# servusb.net
KiCad netlist of a schematic drawn in EAGLE
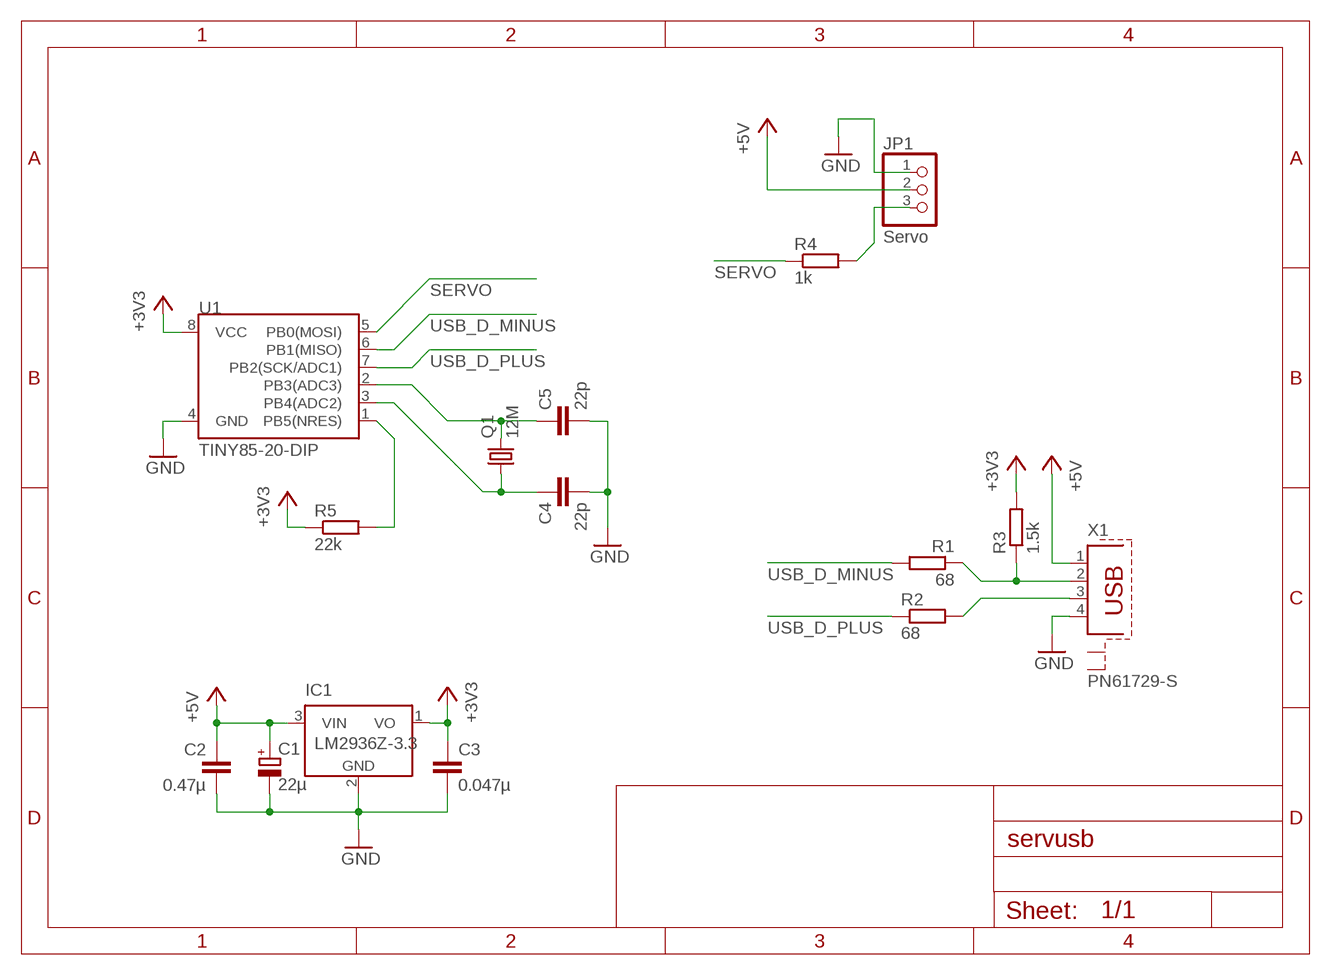
[diagram p0: schematic, sheet 1]

(export (version "E")
  (design (tool "Eeschema 10.0.6"))
  (components
    (comp (ref "C1")
      (value "22µ")
      (footprint "eagle-import:E2,5-6")
      (libsource (lib "eagle-import") (part "CPOL-EUE2.5-6"))
    )
    (comp (ref "C2")
      (value "0.47µ")
      (footprint "eagle-import:C075-042X103")
      (libsource (lib "eagle-import") (part "C-EU075-042X103"))
    )
    (comp (ref "C3")
      (value "0.047µ")
      (footprint "eagle-import:C050-025X075")
      (libsource (lib "eagle-import") (part "C-EU050-025X075"))
    )
    (comp (ref "C4")
      (value "22p")
      (footprint "eagle-import:C025-024X044")
      (libsource (lib "eagle-import") (part "C-EU025-024X044"))
    )
    (comp (ref "C5")
      (value "22p")
      (footprint "eagle-import:C025-024X044")
      (libsource (lib "eagle-import") (part "C-EU025-024X044"))
    )
    (comp (ref "IC1")
      (value "LM2936Z-3.3")
      (footprint "eagle-import:TO92")
      (fields (field (name "MF") "NATIONAL SEMICONDUCTOR") (field (name "MPN") "LM2936Z-3.3/NOPB"))
      (libsource (lib "eagle-import") (part "LM2936?Z-3.3"))
    )
    (comp (ref "JP1")
      (value "Servo")
      (footprint "eagle-import:1X03")
      (libsource (lib "eagle-import") (part "PINHD-1X3"))
    )
    (comp (ref "Q1")
      (value "12M")
      (footprint "eagle-import:HC49_S")
      (libsource (lib "eagle-import") (part "CRYSTALHC49S"))
    )
    (comp (ref "R1")
      (value "68")
      (footprint "eagle-import:0204_7")
      (libsource (lib "eagle-import") (part "R-EU_0204/7"))
    )
    (comp (ref "R2")
      (value "68")
      (footprint "eagle-import:0204_7")
      (libsource (lib "eagle-import") (part "R-EU_0204/7"))
    )
    (comp (ref "R3")
      (value "1.5k")
      (footprint "eagle-import:0204_7")
      (libsource (lib "eagle-import") (part "R-EU_0204/7"))
    )
    (comp (ref "R4")
      (value "1k")
      (footprint "eagle-import:0204_7")
      (libsource (lib "eagle-import") (part "R-EU_0204/7"))
    )
    (comp (ref "R5")
      (value "22k")
      (footprint "eagle-import:0204_7")
      (libsource (lib "eagle-import") (part "R-EU_0204/7"))
    )
    (comp (ref "U1")
      (value "TINY85-20-DIP")
      (footprint "eagle-import:DIP08")
      (libsource (lib "eagle-import") (part "ATTINY45TINY85-20-DIP"))
    )
    (comp (ref "X1")
      (value "PN61729-S")
      (footprint "eagle-import:PN61729-S")
      (libsource (lib "eagle-import") (part "PN61729-S"))
    )
  )
  (nets
    (net (code "1") (name "+3V3") (class "Default")
      (node (ref "C3") (pin "1") (pinfunction "1_1") (pintype "passive"))
      (node (ref "IC1") (pin "1") (pinfunction "VO_1") (pintype "passive"))
      (node (ref "R3") (pin "2") (pinfunction "2_2") (pintype "passive"))
      (node (ref "R5") (pin "1") (pinfunction "1_1") (pintype "passive"))
      (node (ref "U1") (pin "8") (pinfunction "VCC_8") (pintype "bidirectional"))
    )
    (net (code "2") (name "+5V") (class "Default")
      (node (ref "C1") (pin "+") (pinfunction "+_+") (pintype "passive"))
      (node (ref "C2") (pin "1") (pinfunction "1_1") (pintype "passive"))
      (node (ref "IC1") (pin "3") (pinfunction "VIN_3") (pintype "input"))
      (node (ref "JP1") (pin "2") (pinfunction "2_2") (pintype "passive"))
      (node (ref "X1") (pin "1") (pinfunction "1_1") (pintype "passive"))
    )
    (net (code "3") (name "/SERVO") (class "Default")
      (node (ref "R4") (pin "1") (pinfunction "1_1") (pintype "passive"))
      (node (ref "U1") (pin "5") (pinfunction "PB0(MOSI)_5") (pintype "bidirectional"))
    )
    (net (code "4") (name "/USB_D_MINUS") (class "Default")
      (node (ref "R1") (pin "2") (pinfunction "2_2") (pintype "passive"))
      (node (ref "U1") (pin "6") (pinfunction "PB1(MISO)_6") (pintype "bidirectional"))
    )
    (net (code "5") (name "/USB_D_PLUS") (class "Default")
      (node (ref "R2") (pin "1") (pinfunction "1_1") (pintype "passive"))
      (node (ref "U1") (pin "7") (pinfunction "PB2(SCK/ADC1)_7") (pintype "bidirectional"))
    )
    (net (code "6") (name "GND") (class "Default")
      (node (ref "C1") (pin "-") (pinfunction "-_-") (pintype "passive"))
      (node (ref "C2") (pin "2") (pinfunction "2_2") (pintype "passive"))
      (node (ref "C3") (pin "2") (pinfunction "2_2") (pintype "passive"))
      (node (ref "C4") (pin "2") (pinfunction "2_2") (pintype "passive"))
      (node (ref "C5") (pin "2") (pinfunction "2_2") (pintype "passive"))
      (node (ref "IC1") (pin "2") (pinfunction "GND_2") (pintype "passive"))
      (node (ref "JP1") (pin "1") (pinfunction "1_1") (pintype "passive"))
      (node (ref "U1") (pin "4") (pinfunction "GND_4") (pintype "bidirectional"))
      (node (ref "X1") (pin "4") (pinfunction "4_4") (pintype "passive"))
    )
    (net (code "7") (name "Net-(JP1-Pad3)") (class "Default")
      (node (ref "JP1") (pin "3") (pinfunction "3_3") (pintype "passive"))
      (node (ref "R4") (pin "2") (pinfunction "2_2") (pintype "passive"))
    )
    (net (code "8") (name "Net-(R1-Pad1)") (class "Default")
      (node (ref "R1") (pin "1") (pinfunction "1_1") (pintype "passive"))
      (node (ref "R3") (pin "1") (pinfunction "1_1") (pintype "passive"))
      (node (ref "X1") (pin "2") (pinfunction "2_2") (pintype "passive"))
    )
    (net (code "9") (name "Net-(R2-Pad2)") (class "Default")
      (node (ref "R2") (pin "2") (pinfunction "2_2") (pintype "passive"))
      (node (ref "X1") (pin "3") (pinfunction "3_3") (pintype "passive"))
    )
    (net (code "10") (name "Net-(U1-PB3(ADC3))") (class "Default")
      (node (ref "C5") (pin "1") (pinfunction "1_1") (pintype "passive"))
      (node (ref "Q1") (pin "2") (pinfunction "2_2") (pintype "passive"))
      (node (ref "U1") (pin "2") (pinfunction "PB3(ADC3)_2") (pintype "bidirectional"))
    )
    (net (code "11") (name "Net-(U1-PB4(ADC2))") (class "Default")
      (node (ref "C4") (pin "1") (pinfunction "1_1") (pintype "passive"))
      (node (ref "Q1") (pin "1") (pinfunction "1_1") (pintype "passive"))
      (node (ref "U1") (pin "3") (pinfunction "PB4(ADC2)_3") (pintype "bidirectional"))
    )
    (net (code "12") (name "Net-(U1-PB5(NRES))") (class "Default")
      (node (ref "R5") (pin "2") (pinfunction "2_2") (pintype "passive"))
      (node (ref "U1") (pin "1") (pinfunction "PB5(NRES)_1") (pintype "bidirectional"))
    )
    (net (code "13") (name "unconnected-(X1-PadS1)") (class "Default")
      (node (ref "X1") (pin "S1") (pinfunction "S1_S1") (pintype "passive"))
    )
    (net (code "14") (name "unconnected-(X1-PadS2)") (class "Default")
      (node (ref "X1") (pin "S2") (pinfunction "S2_S2") (pintype "passive"))
    )
  )
)
